# drs.net
KiCad netlist of a schematic drawn in EAGLE
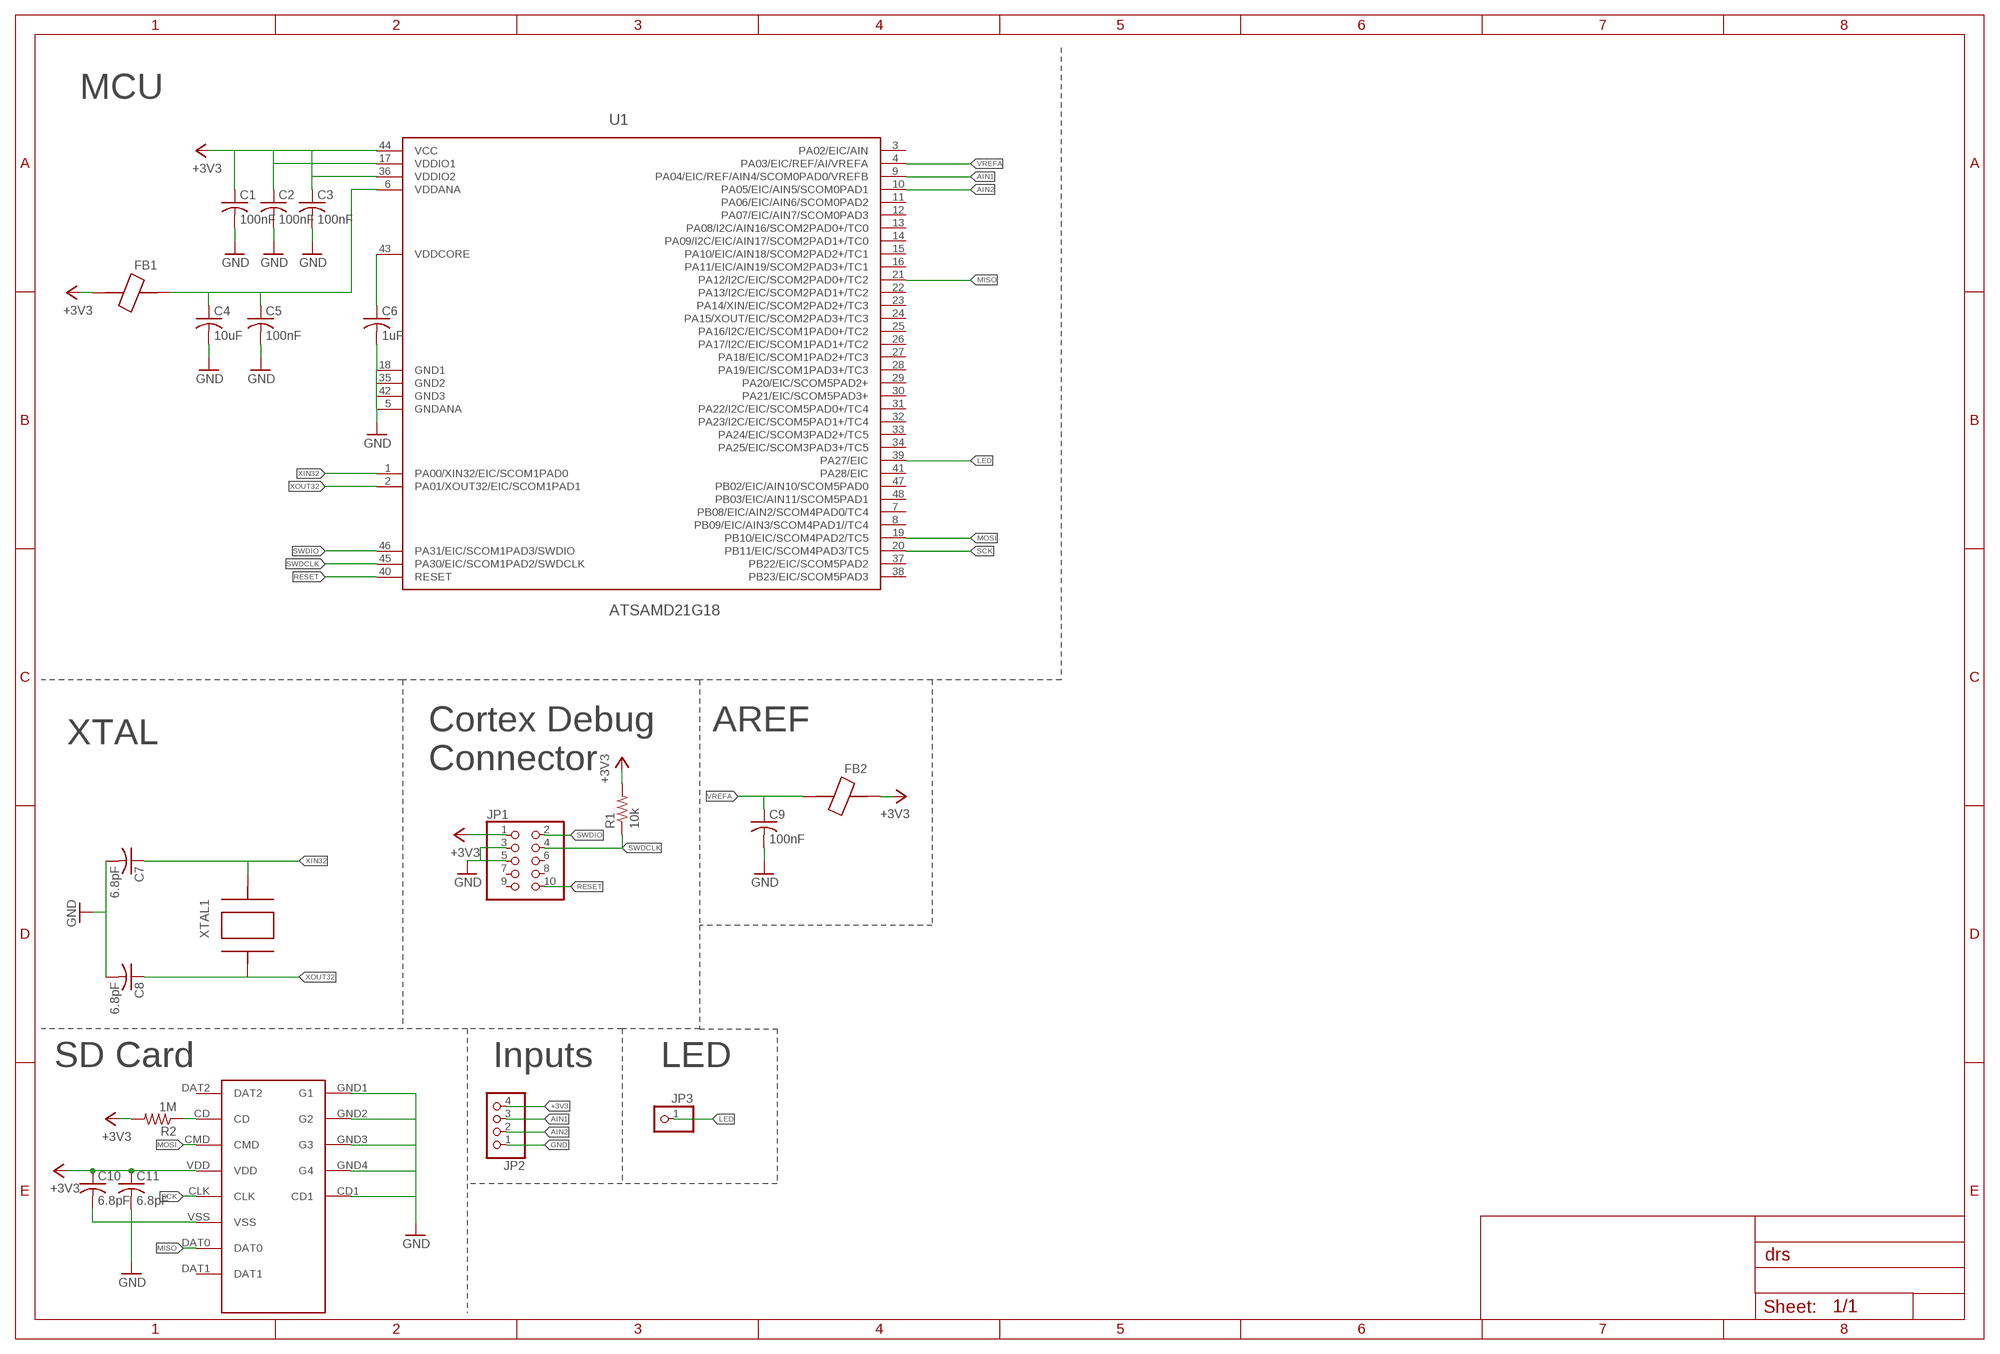
[diagram p0: schematic, sheet 1]

(export (version "E")
  (design (tool "Eeschema 10.0.6"))
  (components
    (comp (ref "C1")
      (value "100nF")
      (footprint "eagle-import:C0603")
      (libsource (lib "eagle-import") (part "C-USC0603"))
    )
    (comp (ref "C2")
      (value "100nF")
      (footprint "eagle-import:C0603")
      (libsource (lib "eagle-import") (part "C-USC0603"))
    )
    (comp (ref "C3")
      (value "100nF")
      (footprint "eagle-import:C0603")
      (libsource (lib "eagle-import") (part "C-USC0603"))
    )
    (comp (ref "C4")
      (value "10uF")
      (footprint "eagle-import:C0603")
      (libsource (lib "eagle-import") (part "C-USC0603"))
    )
    (comp (ref "C5")
      (value "100nF")
      (footprint "eagle-import:C0603")
      (libsource (lib "eagle-import") (part "C-USC0603"))
    )
    (comp (ref "C6")
      (value "1uF")
      (footprint "eagle-import:C0603")
      (libsource (lib "eagle-import") (part "C-USC0603"))
    )
    (comp (ref "C7")
      (value "6.8pF")
      (footprint "eagle-import:C0603")
      (libsource (lib "eagle-import") (part "C-USC0603"))
    )
    (comp (ref "C8")
      (value "6.8pF")
      (footprint "eagle-import:C0603")
      (libsource (lib "eagle-import") (part "C-USC0603"))
    )
    (comp (ref "C9")
      (value "100nF")
      (footprint "eagle-import:C0603")
      (libsource (lib "eagle-import") (part "C-USC0603"))
    )
    (comp (ref "C10")
      (value "6.8pF")
      (footprint "eagle-import:C0603")
      (libsource (lib "eagle-import") (part "C-USC0603"))
    )
    (comp (ref "C11")
      (value "6.8pF")
      (footprint "eagle-import:C0603")
      (libsource (lib "eagle-import") (part "C-USC0603"))
    )
    (comp (ref "FB1")
      (value "FERRITE_BEAD-0603")
      (footprint "eagle-import:0603")
      (libsource (lib "eagle-import") (part "FERRITE_BEAD-0603"))
    )
    (comp (ref "FB2")
      (value "FERRITE_BEAD-0603")
      (footprint "eagle-import:0603")
      (libsource (lib "eagle-import") (part "FERRITE_BEAD-0603"))
    )
    (comp (ref "JP1")
      (value "PINHD-2X5")
      (footprint "eagle-import:2X05")
      (libsource (lib "eagle-import") (part "PINHD-2X5"))
    )
    (comp (ref "JP2")
      (value "PINHD-1X4")
      (footprint "eagle-import:1X04")
      (libsource (lib "eagle-import") (part "PINHD-1X4"))
    )
    (comp (ref "JP3")
      (value "PINHD-1X1")
      (footprint "eagle-import:1X01")
      (libsource (lib "eagle-import") (part "PINHD-1X1"))
    )
    (comp (ref "R1")
      (value "10k")
      (footprint "eagle-import:R0603")
      (libsource (lib "eagle-import") (part "R-US_R0603"))
    )
    (comp (ref "R2")
      (value "1M")
      (footprint "eagle-import:R0603")
      (libsource (lib "eagle-import") (part "R-US_R0603"))
    )
    (comp (ref "U$1")
      (value "MICRO_SD")
      (footprint "eagle-import:MICRO_SD_HINGED")
      (libsource (lib "eagle-import") (part "MICRO_SD"))
    )
    (comp (ref "U1")
      (value "ATSAMD21G18")
      (footprint "eagle-import:48-TQFP")
      (libsource (lib "eagle-import") (part "ATSAMD21G18"))
    )
    (comp (ref "XTAL1")
      (value "ABS07AIG-32.768KHZ-1-T")
      (footprint "eagle-import:2-SMD")
      (libsource (lib "eagle-import") (part "ABS07AIG-32.768KHZ-1-T"))
    )
  )
  (nets
    (net (code "1") (name "+3V3") (class "Default")
      (node (ref "C1") (pin "1") (pinfunction "1_1") (pintype "passive"))
      (node (ref "C10") (pin "1") (pinfunction "1_1") (pintype "passive"))
      (node (ref "C11") (pin "1") (pinfunction "1_1") (pintype "passive"))
      (node (ref "C2") (pin "1") (pinfunction "1_1") (pintype "passive"))
      (node (ref "C3") (pin "1") (pinfunction "1_1") (pintype "passive"))
      (node (ref "FB1") (pin "1") (pinfunction "P$1_1") (pintype "passive"))
      (node (ref "FB2") (pin "2") (pinfunction "P$2_2") (pintype "passive"))
      (node (ref "JP1") (pin "1") (pinfunction "1_1") (pintype "passive"))
      (node (ref "JP2") (pin "4") (pinfunction "4_4") (pintype "passive"))
      (node (ref "R1") (pin "2") (pinfunction "2_2") (pintype "passive"))
      (node (ref "R2") (pin "2") (pinfunction "2_2") (pintype "passive"))
      (node (ref "U$1") (pin "VDD") (pinfunction "VDD_VDD") (pintype "bidirectional"))
      (node (ref "U1") (pin "17") (pinfunction "VDDIO1_17") (pintype "bidirectional"))
      (node (ref "U1") (pin "36") (pinfunction "VDDIO2_36") (pintype "bidirectional"))
      (node (ref "U1") (pin "44") (pinfunction "VCC_44") (pintype "bidirectional"))
    )
    (net (code "2") (name "AIN1") (class "Default")
      (node (ref "JP2") (pin "3") (pinfunction "3_3") (pintype "passive"))
      (node (ref "U1") (pin "9") (pinfunction "PA04/EIC/REF/AIN4/SCOM0PAD0/VREFB_9") (pintype "bidirectional"))
    )
    (net (code "3") (name "AIN2") (class "Default")
      (node (ref "JP2") (pin "2") (pinfunction "2_2") (pintype "passive"))
      (node (ref "U1") (pin "10") (pinfunction "PA05/EIC/AIN5/SCOM0PAD1_10") (pintype "bidirectional"))
    )
    (net (code "4") (name "GND") (class "Default")
      (node (ref "C1") (pin "2") (pinfunction "2_2") (pintype "passive"))
      (node (ref "C10") (pin "2") (pinfunction "2_2") (pintype "passive"))
      (node (ref "C11") (pin "2") (pinfunction "2_2") (pintype "passive"))
      (node (ref "C2") (pin "2") (pinfunction "2_2") (pintype "passive"))
      (node (ref "C3") (pin "2") (pinfunction "2_2") (pintype "passive"))
      (node (ref "C4") (pin "2") (pinfunction "2_2") (pintype "passive"))
      (node (ref "C5") (pin "2") (pinfunction "2_2") (pintype "passive"))
      (node (ref "C6") (pin "2") (pinfunction "2_2") (pintype "passive"))
      (node (ref "C7") (pin "2") (pinfunction "2_2") (pintype "passive"))
      (node (ref "C8") (pin "2") (pinfunction "2_2") (pintype "passive"))
      (node (ref "C9") (pin "2") (pinfunction "2_2") (pintype "passive"))
      (node (ref "JP1") (pin "5") (pinfunction "5_5") (pintype "passive"))
      (node (ref "JP2") (pin "1") (pinfunction "1_1") (pintype "passive"))
      (node (ref "U$1") (pin "CD1") (pinfunction "CD1_CD1") (pintype "bidirectional"))
      (node (ref "U$1") (pin "GND1") (pinfunction "G1_GND1") (pintype "bidirectional"))
      (node (ref "U$1") (pin "GND2") (pinfunction "G2_GND2") (pintype "bidirectional"))
      (node (ref "U$1") (pin "GND3") (pinfunction "G3_GND3") (pintype "bidirectional"))
      (node (ref "U$1") (pin "GND4") (pinfunction "G4_GND4") (pintype "bidirectional"))
      (node (ref "U$1") (pin "VSS") (pinfunction "VSS_VSS") (pintype "bidirectional"))
      (node (ref "U1") (pin "18") (pinfunction "GND1_18") (pintype "bidirectional"))
      (node (ref "U1") (pin "35") (pinfunction "GND2_35") (pintype "bidirectional"))
      (node (ref "U1") (pin "42") (pinfunction "GND3_42") (pintype "bidirectional"))
      (node (ref "U1") (pin "5") (pinfunction "GNDANA_5") (pintype "bidirectional"))
    )
    (net (code "5") (name "LED") (class "Default")
      (node (ref "JP3") (pin "1") (pinfunction "1_1") (pintype "passive"))
      (node (ref "U1") (pin "39") (pinfunction "PA27/EIC_39") (pintype "bidirectional"))
    )
    (net (code "6") (name "MISO") (class "Default")
      (node (ref "U$1") (pin "DAT0") (pinfunction "DAT0_DAT0") (pintype "bidirectional"))
      (node (ref "U1") (pin "21") (pinfunction "PA12/I2C/EIC/SCOM2PAD0+/TC2_21") (pintype "bidirectional"))
    )
    (net (code "7") (name "MOSI") (class "Default")
      (node (ref "U$1") (pin "CMD") (pinfunction "CMD_CMD") (pintype "bidirectional"))
      (node (ref "U1") (pin "19") (pinfunction "PB10/EIC/SCOM4PAD2/TC5_19") (pintype "bidirectional"))
    )
    (net (code "8") (name "Net-(FB1-P$2)") (class "Default")
      (node (ref "C4") (pin "1") (pinfunction "1_1") (pintype "passive"))
      (node (ref "C5") (pin "1") (pinfunction "1_1") (pintype "passive"))
      (node (ref "FB1") (pin "2") (pinfunction "P$2_2") (pintype "passive"))
      (node (ref "U1") (pin "6") (pinfunction "VDDANA_6") (pintype "bidirectional"))
    )
    (net (code "9") (name "Net-(R2-Pad1)") (class "Default")
      (node (ref "R2") (pin "1") (pinfunction "1_1") (pintype "passive"))
      (node (ref "U$1") (pin "CD") (pinfunction "CD_CD") (pintype "bidirectional"))
    )
    (net (code "10") (name "Net-(U1-VDDCORE)") (class "Default")
      (node (ref "C6") (pin "1") (pinfunction "1_1") (pintype "passive"))
      (node (ref "U1") (pin "43") (pinfunction "VDDCORE_43") (pintype "bidirectional"))
    )
    (net (code "11") (name "RESET") (class "Default")
      (node (ref "JP1") (pin "10") (pinfunction "10_10") (pintype "passive"))
      (node (ref "U1") (pin "40") (pinfunction "RESET_40") (pintype "bidirectional"))
    )
    (net (code "12") (name "SCK") (class "Default")
      (node (ref "U$1") (pin "CLK") (pinfunction "CLK_CLK") (pintype "bidirectional"))
      (node (ref "U1") (pin "20") (pinfunction "PB11/EIC/SCOM4PAD3/TC5_20") (pintype "bidirectional"))
    )
    (net (code "13") (name "SWDCLK") (class "Default")
      (node (ref "JP1") (pin "4") (pinfunction "4_4") (pintype "passive"))
      (node (ref "R1") (pin "1") (pinfunction "1_1") (pintype "passive"))
      (node (ref "U1") (pin "45") (pinfunction "PA30/EIC/SCOM1PAD2/SWDCLK_45") (pintype "bidirectional"))
    )
    (net (code "14") (name "SWDIO") (class "Default")
      (node (ref "JP1") (pin "2") (pinfunction "2_2") (pintype "passive"))
      (node (ref "U1") (pin "46") (pinfunction "PA31/EIC/SCOM1PAD3/SWDIO_46") (pintype "bidirectional"))
    )
    (net (code "15") (name "VREFA") (class "Default")
      (node (ref "C9") (pin "1") (pinfunction "1_1") (pintype "passive"))
      (node (ref "FB2") (pin "1") (pinfunction "P$1_1") (pintype "passive"))
      (node (ref "U1") (pin "4") (pinfunction "PA03/EIC/REF/AI/VREFA_4") (pintype "bidirectional"))
    )
    (net (code "16") (name "XIN32") (class "Default")
      (node (ref "C7") (pin "1") (pinfunction "1_1") (pintype "passive"))
      (node (ref "U1") (pin "1") (pinfunction "PA00/XIN32/EIC/SCOM1PAD0_1") (pintype "bidirectional"))
      (node (ref "XTAL1") (pin "P2") (pinfunction "2_P2") (pintype "bidirectional"))
    )
    (net (code "17") (name "XOUT32") (class "Default")
      (node (ref "C8") (pin "1") (pinfunction "1_1") (pintype "passive"))
      (node (ref "U1") (pin "2") (pinfunction "PA01/XOUT32/EIC/SCOM1PAD1_2") (pintype "bidirectional"))
      (node (ref "XTAL1") (pin "P1") (pinfunction "1_P1") (pintype "bidirectional"))
    )
    (net (code "18") (name "unconnected-(JP1-Pad3)") (class "Default")
      (node (ref "JP1") (pin "3") (pinfunction "3_3") (pintype "passive"))
    )
    (net (code "19") (name "unconnected-(JP1-Pad6)") (class "Default")
      (node (ref "JP1") (pin "6") (pinfunction "6_6") (pintype "passive"))
    )
    (net (code "20") (name "unconnected-(JP1-Pad7)") (class "Default")
      (node (ref "JP1") (pin "7") (pinfunction "7_7") (pintype "passive"))
    )
    (net (code "21") (name "unconnected-(JP1-Pad8)") (class "Default")
      (node (ref "JP1") (pin "8") (pinfunction "8_8") (pintype "passive"))
    )
    (net (code "22") (name "unconnected-(JP1-Pad9)") (class "Default")
      (node (ref "JP1") (pin "9") (pinfunction "9_9") (pintype "passive"))
    )
    (net (code "23") (name "unconnected-(U$1-PadDAT1)") (class "Default")
      (node (ref "U$1") (pin "DAT1") (pinfunction "DAT1_DAT1") (pintype "bidirectional"))
    )
    (net (code "24") (name "unconnected-(U$1-PadDAT2)") (class "Default")
      (node (ref "U$1") (pin "DAT2") (pinfunction "DAT2_DAT2") (pintype "bidirectional"))
    )
    (net (code "25") (name "unconnected-(U1-PA02{slash}EIC{slash}AIN-Pad3)") (class "Default")
      (node (ref "U1") (pin "3") (pinfunction "PA02/EIC/AIN_3") (pintype "bidirectional"))
    )
    (net (code "26") (name "unconnected-(U1-PA06{slash}EIC{slash}AIN6{slash}SCOM0PAD2-Pad11)") (class "Default")
      (node (ref "U1") (pin "11") (pinfunction "PA06/EIC/AIN6/SCOM0PAD2_11") (pintype "bidirectional"))
    )
    (net (code "27") (name "unconnected-(U1-PA07{slash}EIC{slash}AIN7{slash}SCOM0PAD3-Pad12)") (class "Default")
      (node (ref "U1") (pin "12") (pinfunction "PA07/EIC/AIN7/SCOM0PAD3_12") (pintype "bidirectional"))
    )
    (net (code "28") (name "unconnected-(U1-PA08{slash}I2C{slash}AIN16{slash}SCOM2PAD0+{slash}TC0-Pad13)") (class "Default")
      (node (ref "U1") (pin "13") (pinfunction "PA08/I2C/AIN16/SCOM2PAD0+/TC0_13") (pintype "bidirectional"))
    )
    (net (code "29") (name "unconnected-(U1-PA09{slash}I2C{slash}EIC{slash}AIN17{slash}SCOM2PAD1+{slash}TC0-Pad14)") (class "Default")
      (node (ref "U1") (pin "14") (pinfunction "PA09/I2C/EIC/AIN17/SCOM2PAD1+/TC0_14") (pintype "bidirectional"))
    )
    (net (code "30") (name "unconnected-(U1-PA10{slash}EIC{slash}AIN18{slash}SCOM2PAD2+{slash}TC1-Pad15)") (class "Default")
      (node (ref "U1") (pin "15") (pinfunction "PA10/EIC/AIN18/SCOM2PAD2+/TC1_15") (pintype "bidirectional"))
    )
    (net (code "31") (name "unconnected-(U1-PA11{slash}EIC{slash}AIN19{slash}SCOM2PAD3+{slash}TC1-Pad16)") (class "Default")
      (node (ref "U1") (pin "16") (pinfunction "PA11/EIC/AIN19/SCOM2PAD3+/TC1_16") (pintype "bidirectional"))
    )
    (net (code "32") (name "unconnected-(U1-PA13{slash}I2C{slash}EIC{slash}SCOM2PAD1+{slash}TC2-Pad22)") (class "Default")
      (node (ref "U1") (pin "22") (pinfunction "PA13/I2C/EIC/SCOM2PAD1+/TC2_22") (pintype "bidirectional"))
    )
    (net (code "33") (name "unconnected-(U1-PA14{slash}XIN{slash}EIC{slash}SCOM2PAD2+{slash}TC3-Pad23)") (class "Default")
      (node (ref "U1") (pin "23") (pinfunction "PA14/XIN/EIC/SCOM2PAD2+/TC3_23") (pintype "bidirectional"))
    )
    (net (code "34") (name "unconnected-(U1-PA15{slash}XOUT{slash}EIC{slash}SCOM2PAD3+{slash}TC3-Pad24)") (class "Default")
      (node (ref "U1") (pin "24") (pinfunction "PA15/XOUT/EIC/SCOM2PAD3+/TC3_24") (pintype "bidirectional"))
    )
    (net (code "35") (name "unconnected-(U1-PA16{slash}I2C{slash}EIC{slash}SCOM1PAD0+{slash}TC2-Pad25)") (class "Default")
      (node (ref "U1") (pin "25") (pinfunction "PA16/I2C/EIC/SCOM1PAD0+/TC2_25") (pintype "bidirectional"))
    )
    (net (code "36") (name "unconnected-(U1-PA17{slash}I2C{slash}EIC{slash}SCOM1PAD1+{slash}TC2-Pad26)") (class "Default")
      (node (ref "U1") (pin "26") (pinfunction "PA17/I2C/EIC/SCOM1PAD1+/TC2_26") (pintype "bidirectional"))
    )
    (net (code "37") (name "unconnected-(U1-PA18{slash}EIC{slash}SCOM1PAD2+{slash}TC3-Pad27)") (class "Default")
      (node (ref "U1") (pin "27") (pinfunction "PA18/EIC/SCOM1PAD2+/TC3_27") (pintype "bidirectional"))
    )
    (net (code "38") (name "unconnected-(U1-PA19{slash}EIC{slash}SCOM1PAD3+{slash}TC3-Pad28)") (class "Default")
      (node (ref "U1") (pin "28") (pinfunction "PA19/EIC/SCOM1PAD3+/TC3_28") (pintype "bidirectional"))
    )
    (net (code "39") (name "unconnected-(U1-PA20{slash}EIC{slash}SCOM5PAD2+-Pad29)") (class "Default")
      (node (ref "U1") (pin "29") (pinfunction "PA20/EIC/SCOM5PAD2+_29") (pintype "bidirectional"))
    )
    (net (code "40") (name "unconnected-(U1-PA21{slash}EIC{slash}SCOM5PAD3+-Pad30)") (class "Default")
      (node (ref "U1") (pin "30") (pinfunction "PA21/EIC/SCOM5PAD3+_30") (pintype "bidirectional"))
    )
    (net (code "41") (name "unconnected-(U1-PA22{slash}I2C{slash}EIC{slash}SCOM5PAD0+{slash}TC4-Pad31)") (class "Default")
      (node (ref "U1") (pin "31") (pinfunction "PA22/I2C/EIC/SCOM5PAD0+/TC4_31") (pintype "bidirectional"))
    )
    (net (code "42") (name "unconnected-(U1-PA23{slash}I2C{slash}EIC{slash}SCOM5PAD1+{slash}TC4-Pad32)") (class "Default")
      (node (ref "U1") (pin "32") (pinfunction "PA23/I2C/EIC/SCOM5PAD1+/TC4_32") (pintype "bidirectional"))
    )
    (net (code "43") (name "unconnected-(U1-PA24{slash}EIC{slash}SCOM3PAD2+{slash}TC5-Pad33)") (class "Default")
      (node (ref "U1") (pin "33") (pinfunction "PA24/EIC/SCOM3PAD2+/TC5_33") (pintype "bidirectional"))
    )
    (net (code "44") (name "unconnected-(U1-PA25{slash}EIC{slash}SCOM3PAD3+{slash}TC5-Pad34)") (class "Default")
      (node (ref "U1") (pin "34") (pinfunction "PA25/EIC/SCOM3PAD3+/TC5_34") (pintype "bidirectional"))
    )
    (net (code "45") (name "unconnected-(U1-PA28{slash}EIC-Pad41)") (class "Default")
      (node (ref "U1") (pin "41") (pinfunction "PA28/EIC_41") (pintype "bidirectional"))
    )
    (net (code "46") (name "unconnected-(U1-PB02{slash}EIC{slash}AIN10{slash}SCOM5PAD0-Pad47)") (class "Default")
      (node (ref "U1") (pin "47") (pinfunction "PB02/EIC/AIN10/SCOM5PAD0_47") (pintype "bidirectional"))
    )
    (net (code "47") (name "unconnected-(U1-PB03{slash}EIC{slash}AIN11{slash}SCOM5PAD1-Pad48)") (class "Default")
      (node (ref "U1") (pin "48") (pinfunction "PB03/EIC/AIN11/SCOM5PAD1_48") (pintype "bidirectional"))
    )
    (net (code "48") (name "unconnected-(U1-PB08{slash}EIC{slash}AIN2{slash}SCOM4PAD0{slash}TC4-Pad7)") (class "Default")
      (node (ref "U1") (pin "7") (pinfunction "PB08/EIC/AIN2/SCOM4PAD0/TC4_7") (pintype "bidirectional"))
    )
    (net (code "49") (name "unconnected-(U1-PB09{slash}EIC{slash}AIN3{slash}SCOM4PAD1{slash}{slash}TC4-Pad8)") (class "Default")
      (node (ref "U1") (pin "8") (pinfunction "PB09/EIC/AIN3/SCOM4PAD1//TC4_8") (pintype "bidirectional"))
    )
    (net (code "50") (name "unconnected-(U1-PB22{slash}EIC{slash}SCOM5PAD2-Pad37)") (class "Default")
      (node (ref "U1") (pin "37") (pinfunction "PB22/EIC/SCOM5PAD2_37") (pintype "bidirectional"))
    )
    (net (code "51") (name "unconnected-(U1-PB23{slash}EIC{slash}SCOM5PAD3-Pad38)") (class "Default")
      (node (ref "U1") (pin "38") (pinfunction "PB23/EIC/SCOM5PAD3_38") (pintype "bidirectional"))
    )
  )
)
